# design.net
KiCad netlist of a schematic drawn in Altium Designer
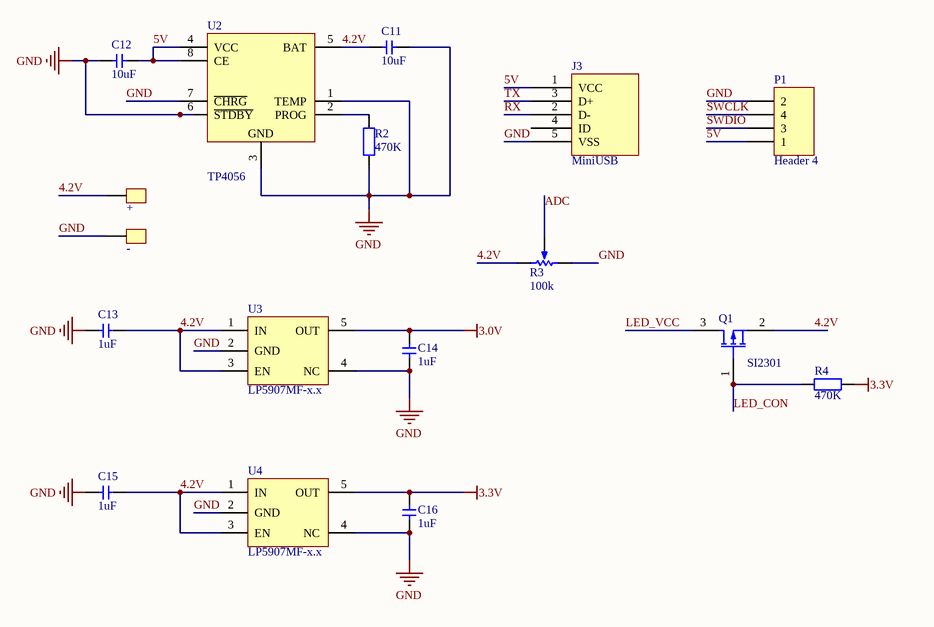
[diagram p0: 电源.SchDoc]

(export (version "E")
  (design (tool "Eeschema 10.0.6"))
  (components
    (comp (ref "+")
      (value "pad")
      (footprint "pad_3x3")
      (description "焊盘接口")
      (libsource (lib "fszhang") (part "pad_3x3"))
    )
    (comp (ref "-")
      (value "pad")
      (footprint "pad_3x3")
      (description "焊盘接口")
      (libsource (lib "fszhang") (part "pad_3x3"))
    )
    (comp (ref "C11")
      (value "10uF")
      (footprint "0805-2")
      (description "无极性电容")
      (fields (field (name "Comment") "Cap") (field (name "PUBLISHER") "Altium Limited"))
      (libsource (lib "fszhang") (part "Cap"))
    )
    (comp (ref "C12")
      (value "10uF")
      (footprint "0805-2")
      (description "无极性电容")
      (fields (field (name "Comment") "Cap") (field (name "PUBLISHER") "Altium Limited"))
      (libsource (lib "fszhang") (part "Cap"))
    )
    (comp (ref "C13")
      (value "1uF")
      (footprint "0805-2")
      (description "无极性电容")
      (fields (field (name "Comment") "Cap") (field (name "PUBLISHER") "Altium Limited"))
      (libsource (lib "fszhang") (part "Cap"))
    )
    (comp (ref "C14")
      (value "1uF")
      (footprint "0805-2")
      (description "无极性电容")
      (fields (field (name "Comment") "Cap") (field (name "PUBLISHER") "Altium Limited"))
      (libsource (lib "fszhang") (part "Cap"))
    )
    (comp (ref "C15")
      (value "1uF")
      (footprint "0805-2")
      (description "无极性电容")
      (fields (field (name "Comment") "Cap") (field (name "PUBLISHER") "Altium Limited"))
      (libsource (lib "fszhang") (part "Cap"))
    )
    (comp (ref "C16")
      (value "1uF")
      (footprint "0805-2")
      (description "无极性电容")
      (fields (field (name "Comment") "Cap") (field (name "PUBLISHER") "Altium Limited"))
      (libsource (lib "fszhang") (part "Cap"))
    )
    (comp (ref "J3")
      (value "MiniUSB")
      (footprint "MINI USB")
      (description "MiniUSB母座")
      (libsource (lib "fszhang") (part "MiniUSB"))
    )
    (comp (ref "P1")
      (value "Header 4")
      (footprint "HDR1X4")
      (description "Header, 4-Pin")
      (fields (field (name "PUBLISHER") "Altium Limited"))
      (libsource (lib "Miscellaneous Connectors") (part "Header 4"))
    )
    (comp (ref "Q1")
      (value "SI2301")
      (footprint "SOT-23")
      (description "PMOS")
      (libsource (lib "fszhang") (part "SI2301"))
    )
    (comp (ref "R2")
      (value "470K")
      (footprint "0805-2")
      (description "贴片电阻")
      (fields (field (name "Comment") "Res1") (field (name "PUBLISHER") "Altium Limited"))
      (libsource (lib "") (part "Res1_1"))
    )
    (comp (ref "R3")
      (value "100k")
      (footprint "3362P")
      (description "精密可调单圈电阻器")
      (fields (field (name "Comment") "3362"))
      (libsource (lib "fszhang") (part "3362"))
    )
    (comp (ref "R4")
      (value "470K")
      (footprint "0805-2")
      (description "贴片电阻")
      (fields (field (name "Comment") "Res1") (field (name "PUBLISHER") "Altium Limited"))
      (libsource (lib "fszhang") (part "Res1"))
    )
    (comp (ref "U2")
      (value "TP4056")
      (footprint "SOP-8-PP")
      (description "锂电池充电管理")
      (libsource (lib "fszhang") (part "TP4056"))
    )
    (comp (ref "U3")
      (value "LP5907MF-x.x")
      (footprint "SOT-23-5")
      (description "LDO线性稳压器")
      (libsource (lib "fszhang") (part "LP5907MF-x.x"))
    )
    (comp (ref "U4")
      (value "LP5907MF-x.x")
      (footprint "SOT-23-5")
      (description "LDO线性稳压器")
      (libsource (lib "fszhang") (part "LP5907MF-x.x"))
    )
  )
  (nets
    (net (code "1") (name "/4.2V") (class "Default")
      (node (ref "+") (pin "1") (pinfunction "1_1") (pintype "passive"))
      (node (ref "C11") (pin "2") (pinfunction "2_2") (pintype "passive"))
      (node (ref "C13") (pin "1") (pinfunction "1_1") (pintype "passive"))
      (node (ref "C15") (pin "1") (pinfunction "1_1") (pintype "passive"))
      (node (ref "Q1") (pin "2") (pinfunction "S_2") (pintype "passive"))
      (node (ref "R3") (pin "3") (pinfunction "BOT_3") (pintype "passive"))
      (node (ref "U2") (pin "5") (pinfunction "BAT_5") (pintype "passive"))
      (node (ref "U3") (pin "1") (pinfunction "IN_1") (pintype "passive"))
      (node (ref "U3") (pin "3") (pinfunction "EN_3") (pintype "passive"))
      (node (ref "U4") (pin "1") (pinfunction "IN_1") (pintype "passive"))
      (node (ref "U4") (pin "3") (pinfunction "EN_3") (pintype "passive"))
    )
    (net (code "2") (name "/5V") (class "Default")
      (node (ref "C12") (pin "1") (pinfunction "1_1") (pintype "passive"))
      (node (ref "J3") (pin "1") (pinfunction "VCC_1") (pintype "passive"))
      (node (ref "P1") (pin "1") (pinfunction "1_1") (pintype "passive"))
      (node (ref "U2") (pin "4") (pinfunction "VCC_4") (pintype "passive"))
      (node (ref "U2") (pin "8") (pinfunction "CE_8") (pintype "passive"))
    )
    (net (code "3") (name "/ADC") (class "Default")
      (node (ref "R3") (pin "2") (pinfunction "TAP_2") (pintype "passive"))
    )
    (net (code "4") (name "/LED_CON") (class "Default")
      (node (ref "Q1") (pin "1") (pinfunction "G_1") (pintype "passive"))
      (node (ref "R4") (pin "2") (pinfunction "2_2") (pintype "passive"))
    )
    (net (code "5") (name "/LED_VCC") (class "Default")
      (node (ref "Q1") (pin "3") (pinfunction "D_3") (pintype "passive"))
    )
    (net (code "6") (name "/RX") (class "Default")
      (node (ref "J3") (pin "2") (pinfunction "D-_2") (pintype "passive"))
    )
    (net (code "7") (name "/SWCLK") (class "Default")
      (node (ref "P1") (pin "4") (pinfunction "4_4") (pintype "passive"))
    )
    (net (code "8") (name "/SWDIO") (class "Default")
      (node (ref "P1") (pin "3") (pinfunction "3_3") (pintype "passive"))
    )
    (net (code "9") (name "/TX") (class "Default")
      (node (ref "J3") (pin "3") (pinfunction "D+_3") (pintype "passive"))
    )
    (net (code "10") (name "3.0V") (class "Default")
      (node (ref "C14") (pin "2") (pinfunction "2_2") (pintype "passive"))
      (node (ref "U3") (pin "5") (pinfunction "OUT_5") (pintype "passive"))
    )
    (net (code "11") (name "3.3V") (class "Default")
      (node (ref "C16") (pin "2") (pinfunction "2_2") (pintype "passive"))
      (node (ref "R4") (pin "1") (pinfunction "1_1") (pintype "passive"))
      (node (ref "U4") (pin "5") (pinfunction "OUT_5") (pintype "passive"))
    )
    (net (code "12") (name "GND") (class "Default")
      (node (ref "-") (pin "1") (pinfunction "1_1") (pintype "passive"))
      (node (ref "C11") (pin "1") (pinfunction "1_1") (pintype "passive"))
      (node (ref "C12") (pin "2") (pinfunction "2_2") (pintype "passive"))
      (node (ref "C13") (pin "2") (pinfunction "2_2") (pintype "passive"))
      (node (ref "C14") (pin "1") (pinfunction "1_1") (pintype "passive"))
      (node (ref "C15") (pin "2") (pinfunction "2_2") (pintype "passive"))
      (node (ref "C16") (pin "1") (pinfunction "1_1") (pintype "passive"))
      (node (ref "J3") (pin "5") (pinfunction "VSS_5") (pintype "passive"))
      (node (ref "P1") (pin "2") (pinfunction "2_2") (pintype "passive"))
      (node (ref "R2") (pin "1") (pinfunction "1_1") (pintype "passive"))
      (node (ref "R3") (pin "1") (pinfunction "TOP_1") (pintype "passive"))
      (node (ref "U2") (pin "1") (pinfunction "TEMP_1") (pintype "passive"))
      (node (ref "U2") (pin "3") (pinfunction "GND_3") (pintype "passive"))
      (node (ref "U2") (pin "6") (pinfunction "~{STDBY}_6") (pintype "passive"))
      (node (ref "U2") (pin "7") (pinfunction "~{CHRG}_7") (pintype "passive"))
      (node (ref "U3") (pin "2") (pinfunction "GND_2") (pintype "passive"))
      (node (ref "U3") (pin "4") (pinfunction "NC_4") (pintype "passive"))
      (node (ref "U4") (pin "2") (pinfunction "GND_2") (pintype "passive"))
      (node (ref "U4") (pin "4") (pinfunction "NC_4") (pintype "passive"))
    )
    (net (code "13") (name "Net-(U2-PROG)") (class "Default")
      (node (ref "R2") (pin "2") (pinfunction "2_2") (pintype "passive"))
      (node (ref "U2") (pin "2") (pinfunction "PROG_2") (pintype "passive"))
    )
    (net (code "14") (name "unconnected-(J3-ID-Pad4)") (class "Default")
      (node (ref "J3") (pin "4") (pinfunction "ID_4") (pintype "passive"))
    )
  )
)
